# MJ828_-_prod_-_FPC.net
KiCad netlist of a schematic drawn in EAGLE
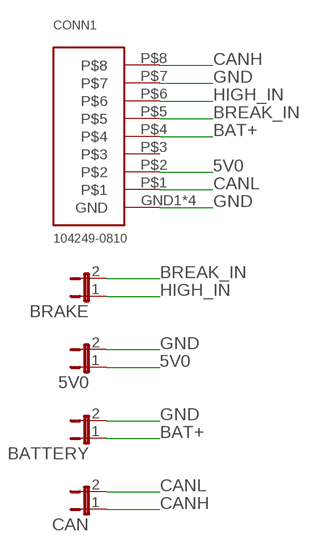
[diagram p0: schematic, sheet 1]

(export (version "E")
  (design (tool "Eeschema 10.0.6"))
  (components
    (comp (ref "5V0")
      (value "JP1E")
      (footprint "eagle-import:JP1")
      (libsource (lib "eagle-import") (part "JP1E"))
    )
    (comp (ref "BATTERY")
      (value "JP1E")
      (footprint "eagle-import:JP1")
      (libsource (lib "eagle-import") (part "JP1E"))
    )
    (comp (ref "BRAKE")
      (value "JP1E")
      (footprint "eagle-import:JP1")
      (libsource (lib "eagle-import") (part "JP1E"))
    )
    (comp (ref "CAN")
      (value "JP1E")
      (footprint "eagle-import:JP1")
      (libsource (lib "eagle-import") (part "JP1E"))
    )
    (comp (ref "CONN1")
      (value "104249-0810")
      (footprint "eagle-import:SMD")
      (libsource (lib "eagle-import") (part "104259-0810"))
    )
  )
  (nets
    (net (code "1") (name "/5V0") (class "Default")
      (node (ref "5V0") (pin "1") (pinfunction "1_1") (pintype "passive"))
      (node (ref "CONN1") (pin "P$2") (pinfunction "P$2_P$2") (pintype "bidirectional"))
    )
    (net (code "2") (name "/BAT+") (class "Default")
      (node (ref "BATTERY") (pin "1") (pinfunction "1_1") (pintype "passive"))
      (node (ref "CONN1") (pin "P$4") (pinfunction "P$4_P$4") (pintype "bidirectional"))
    )
    (net (code "3") (name "/BREAK_IN") (class "Default")
      (node (ref "BRAKE") (pin "2") (pinfunction "2_2") (pintype "passive"))
      (node (ref "CONN1") (pin "P$5") (pinfunction "P$5_P$5") (pintype "bidirectional"))
    )
    (net (code "4") (name "/CANH") (class "Default")
      (node (ref "CAN") (pin "1") (pinfunction "1_1") (pintype "passive"))
      (node (ref "CONN1") (pin "P$8") (pinfunction "P$8_P$8") (pintype "bidirectional"))
    )
    (net (code "5") (name "/CANL") (class "Default")
      (node (ref "CAN") (pin "2") (pinfunction "2_2") (pintype "passive"))
      (node (ref "CONN1") (pin "P$1") (pinfunction "P$1_P$1") (pintype "bidirectional"))
    )
    (net (code "6") (name "/GND") (class "Default")
      (node (ref "5V0") (pin "2") (pinfunction "2_2") (pintype "passive"))
      (node (ref "BATTERY") (pin "2") (pinfunction "2_2") (pintype "passive"))
      (node (ref "CONN1") (pin "GND1") (pinfunction "GND_GND1") (pintype "bidirectional"))
      (node (ref "CONN1") (pin "GND2") (pinfunction "GND_GND2") (pintype "bidirectional"))
      (node (ref "CONN1") (pin "GND3") (pinfunction "GND_GND3") (pintype "bidirectional"))
      (node (ref "CONN1") (pin "GND4") (pinfunction "GND_GND4") (pintype "bidirectional"))
      (node (ref "CONN1") (pin "P$7") (pinfunction "P$7_P$7") (pintype "bidirectional"))
    )
    (net (code "7") (name "/HIGH_IN") (class "Default")
      (node (ref "BRAKE") (pin "1") (pinfunction "1_1") (pintype "passive"))
      (node (ref "CONN1") (pin "P$6") (pinfunction "P$6_P$6") (pintype "bidirectional"))
    )
    (net (code "8") (name "unconnected-(CONN1-PadP$3)") (class "Default")
      (node (ref "CONN1") (pin "P$3") (pinfunction "P$3_P$3") (pintype "bidirectional"))
    )
  )
)
